# untitled.net
KiCad netlist of a schematic drawn in EAGLE
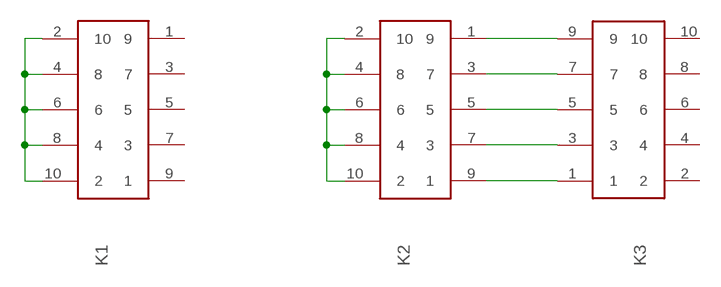
[diagram p0: schematic, sheet 1]

(export (version "E")
  (design (tool "Eeschema 10.0.6"))
  (components
    (comp (ref "K1")
      (value "61201021721")
      (footprint "eagle-import:61201021721")
      (libsource (lib "eagle-import") (part "61201021721"))
    )
    (comp (ref "K2")
      (value "61201021721")
      (footprint "eagle-import:61201021721")
      (libsource (lib "eagle-import") (part "61201021721"))
    )
    (comp (ref "K3")
      (value "612X1020621")
      (footprint "eagle-import:612X1020621")
      (libsource (lib "eagle-import") (part "612X1020621"))
    )
  )
  (nets
    (net (code "1") (name "Net-(K1-10)") (class "Default")
      (node (ref "K1") (pin "10") (pinfunction "2_10") (pintype "passive"))
      (node (ref "K1") (pin "2") (pinfunction "10_2") (pintype "passive"))
      (node (ref "K1") (pin "4") (pinfunction "8_4") (pintype "passive"))
      (node (ref "K1") (pin "6") (pinfunction "6_6") (pintype "passive"))
      (node (ref "K1") (pin "8") (pinfunction "4_8") (pintype "passive"))
    )
    (net (code "2") (name "Net-(K2-1)") (class "Default")
      (node (ref "K2") (pin "9") (pinfunction "1_9") (pintype "passive"))
      (node (ref "K3") (pin "1") (pinfunction "1_1") (pintype "passive"))
    )
    (net (code "3") (name "Net-(K2-3)") (class "Default")
      (node (ref "K2") (pin "7") (pinfunction "3_7") (pintype "passive"))
      (node (ref "K3") (pin "3") (pinfunction "3_3") (pintype "passive"))
    )
    (net (code "4") (name "Net-(K2-7)") (class "Default")
      (node (ref "K2") (pin "3") (pinfunction "7_3") (pintype "passive"))
      (node (ref "K3") (pin "7") (pinfunction "7_7") (pintype "passive"))
    )
    (net (code "5") (name "Net-(K2-9)") (class "Default")
      (node (ref "K2") (pin "1") (pinfunction "9_1") (pintype "passive"))
      (node (ref "K3") (pin "9") (pinfunction "9_9") (pintype "passive"))
    )
    (net (code "6") (name "Net-(K2-10)") (class "Default")
      (node (ref "K2") (pin "10") (pinfunction "2_10") (pintype "passive"))
      (node (ref "K2") (pin "2") (pinfunction "10_2") (pintype "passive"))
      (node (ref "K2") (pin "4") (pinfunction "8_4") (pintype "passive"))
      (node (ref "K2") (pin "6") (pinfunction "6_6") (pintype "passive"))
      (node (ref "K2") (pin "8") (pinfunction "4_8") (pintype "passive"))
    )
    (net (code "7") (name "Net-(K2-Pad5)") (class "Default")
      (node (ref "K2") (pin "5") (pinfunction "5_5") (pintype "passive"))
      (node (ref "K3") (pin "5") (pinfunction "5_5") (pintype "passive"))
    )
    (net (code "8") (name "unconnected-(K1-1-Pad9)") (class "Default")
      (node (ref "K1") (pin "9") (pinfunction "1_9") (pintype "passive"))
    )
    (net (code "9") (name "unconnected-(K1-3-Pad7)") (class "Default")
      (node (ref "K1") (pin "7") (pinfunction "3_7") (pintype "passive"))
    )
    (net (code "10") (name "unconnected-(K1-7-Pad3)") (class "Default")
      (node (ref "K1") (pin "3") (pinfunction "7_3") (pintype "passive"))
    )
    (net (code "11") (name "unconnected-(K1-9-Pad1)") (class "Default")
      (node (ref "K1") (pin "1") (pinfunction "9_1") (pintype "passive"))
    )
    (net (code "12") (name "unconnected-(K1-Pad5)") (class "Default")
      (node (ref "K1") (pin "5") (pinfunction "5_5") (pintype "passive"))
    )
    (net (code "13") (name "unconnected-(K3-Pad2)") (class "Default")
      (node (ref "K3") (pin "2") (pinfunction "2_2") (pintype "passive"))
    )
    (net (code "14") (name "unconnected-(K3-Pad4)") (class "Default")
      (node (ref "K3") (pin "4") (pinfunction "4_4") (pintype "passive"))
    )
    (net (code "15") (name "unconnected-(K3-Pad6)") (class "Default")
      (node (ref "K3") (pin "6") (pinfunction "6_6") (pintype "passive"))
    )
    (net (code "16") (name "unconnected-(K3-Pad8)") (class "Default")
      (node (ref "K3") (pin "8") (pinfunction "8_8") (pintype "passive"))
    )
    (net (code "17") (name "unconnected-(K3-Pad10)") (class "Default")
      (node (ref "K3") (pin "10") (pinfunction "10_10") (pintype "passive"))
    )
  )
)
